# CHANNEL.net
KiCad netlist of a schematic drawn in Altium Designer
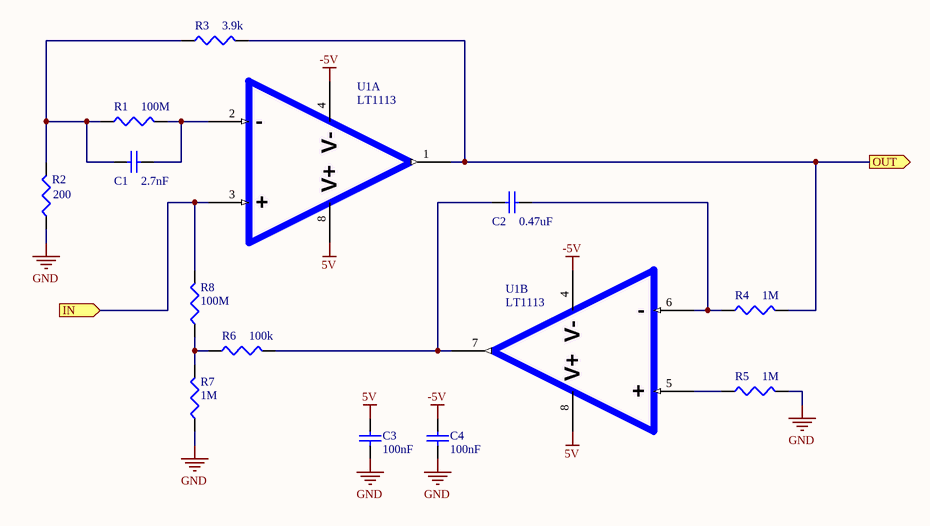
[diagram p0: CHANNEL.SchDoc]

(export (version "E")
  (design (tool "Eeschema 10.0.6"))
  (components
    (comp (ref "C1")
      (value "2.7nF")
      (footprint "1608[0603]")
      (description "Capacitor (Semiconductor SIM Model)")
      (fields (field (name "Comment") "Cap Semi") (field (name "PUBLISHER") "Altium Limited"))
      (libsource (lib "Miscellaneous Devices") (part "Cap Semi"))
    )
    (comp (ref "C2")
      (value "0.47uF")
      (footprint "1608[0603]")
      (description "Capacitor (Semiconductor SIM Model)")
      (fields (field (name "Comment") "Cap Semi") (field (name "PUBLISHER") "Altium Limited"))
      (libsource (lib "Miscellaneous Devices") (part "Cap Semi"))
    )
    (comp (ref "C3")
      (value "100nF")
      (footprint "1608[0603]")
      (description "Capacitor (Semiconductor SIM Model)")
      (fields (field (name "Comment") "Cap Semi") (field (name "PUBLISHER") "Altium Limited"))
      (libsource (lib "Miscellaneous Devices") (part "Cap Semi"))
    )
    (comp (ref "C4")
      (value "100nF")
      (footprint "1608[0603]")
      (description "Capacitor (Semiconductor SIM Model)")
      (fields (field (name "Comment") "Cap Semi") (field (name "PUBLISHER") "Altium Limited"))
      (libsource (lib "Miscellaneous Devices") (part "Cap Semi"))
    )
    (comp (ref "R1")
      (value "100M")
      (footprint "J1-0603")
      (description "Resistor")
      (fields (field (name "Comment") "Res3") (field (name "PUBLISHER") "Altium Limited"))
      (libsource (lib "Miscellaneous Devices") (part "Res3"))
    )
    (comp (ref "R2")
      (value "200")
      (footprint "J1-0603")
      (description "Resistor")
      (fields (field (name "Comment") "Res3") (field (name "PUBLISHER") "Altium Limited"))
      (libsource (lib "Miscellaneous Devices") (part "Res3"))
    )
    (comp (ref "R3")
      (value "3.9k")
      (footprint "J1-0603")
      (description "Resistor")
      (fields (field (name "Comment") "Res3") (field (name "PUBLISHER") "Altium Limited"))
      (libsource (lib "Miscellaneous Devices") (part "Res3"))
    )
    (comp (ref "R4")
      (value "1M")
      (footprint "J1-0603")
      (description "Resistor")
      (fields (field (name "Comment") "Res3") (field (name "PUBLISHER") "Altium Limited"))
      (libsource (lib "Miscellaneous Devices") (part "Res3"))
    )
    (comp (ref "R5")
      (value "1M")
      (footprint "J1-0603")
      (description "Resistor")
      (fields (field (name "Comment") "Res3") (field (name "PUBLISHER") "Altium Limited"))
      (libsource (lib "Miscellaneous Devices") (part "Res3"))
    )
    (comp (ref "R6")
      (value "100k")
      (footprint "J1-0603")
      (description "Resistor")
      (fields (field (name "Comment") "Res3") (field (name "PUBLISHER") "Altium Limited"))
      (libsource (lib "Miscellaneous Devices") (part "Res3"))
    )
    (comp (ref "R7")
      (value "1M")
      (footprint "J1-0603")
      (description "Resistor")
      (fields (field (name "Comment") "Res3") (field (name "PUBLISHER") "Altium Limited"))
      (libsource (lib "Miscellaneous Devices") (part "Res3"))
    )
    (comp (ref "R8")
      (value "100M")
      (footprint "J1-0603")
      (description "Resistor")
      (fields (field (name "Comment") "Res3") (field (name "PUBLISHER") "Altium Limited"))
      (libsource (lib "Miscellaneous Devices") (part "Res3"))
    )
    (comp (ref "U1")
      (value "LT1113")
      (footprint "SO8_L")
      (description "LT1113 Opamp")
      (libsource (lib "Schlib") (part "LT1113"))
    )
  )
  (nets
    (net (code "1") (name "-5V") (class "Default")
      (node (ref "C4") (pin "2") (pinfunction "2_2") (pintype "passive"))
      (node (ref "U1") (pin "4") (pinfunction "V-_4") (pintype "power_in"))
    )
    (net (code "2") (name "/IN") (class "Default")
      (node (ref "R8") (pin "2") (pinfunction "2_2") (pintype "passive"))
      (node (ref "U1") (pin "3") (pinfunction "+_3") (pintype "input"))
    )
    (net (code "3") (name "/OUT") (class "Default")
      (node (ref "R3") (pin "2") (pinfunction "2_2") (pintype "passive"))
      (node (ref "R4") (pin "2") (pinfunction "2_2") (pintype "passive"))
      (node (ref "U1") (pin "1") (pinfunction "OUTA_1") (pintype "output"))
    )
    (net (code "4") (name "5V") (class "Default")
      (node (ref "C3") (pin "2") (pinfunction "2_2") (pintype "passive"))
      (node (ref "U1") (pin "8") (pinfunction "V+_8") (pintype "power_in"))
    )
    (net (code "5") (name "GND") (class "Default")
      (node (ref "C3") (pin "1") (pinfunction "1_1") (pintype "passive"))
      (node (ref "C4") (pin "1") (pinfunction "1_1") (pintype "passive"))
      (node (ref "R2") (pin "1") (pinfunction "1_1") (pintype "passive"))
      (node (ref "R5") (pin "2") (pinfunction "2_2") (pintype "passive"))
      (node (ref "R7") (pin "1") (pinfunction "1_1") (pintype "passive"))
    )
    (net (code "6") (name "Net-(C1-Pad1)") (class "Default")
      (node (ref "C1") (pin "1") (pinfunction "1_1") (pintype "passive"))
      (node (ref "R1") (pin "1") (pinfunction "1_1") (pintype "passive"))
      (node (ref "R2") (pin "2") (pinfunction "2_2") (pintype "passive"))
      (node (ref "R3") (pin "1") (pinfunction "1_1") (pintype "passive"))
    )
    (net (code "7") (name "Net-(R6-Pad1)") (class "Default")
      (node (ref "R6") (pin "1") (pinfunction "1_1") (pintype "passive"))
      (node (ref "R7") (pin "2") (pinfunction "2_2") (pintype "passive"))
      (node (ref "R8") (pin "1") (pinfunction "1_1") (pintype "passive"))
    )
    (net (code "8") (name "Net-(U1A--)") (class "Default")
      (node (ref "C1") (pin "2") (pinfunction "2_2") (pintype "passive"))
      (node (ref "R1") (pin "2") (pinfunction "2_2") (pintype "passive"))
      (node (ref "U1") (pin "2") (pinfunction "-_2") (pintype "input"))
    )
    (net (code "9") (name "Net-(U1B-+)") (class "Default")
      (node (ref "R5") (pin "1") (pinfunction "1_1") (pintype "passive"))
      (node (ref "U1") (pin "5") (pinfunction "+_5") (pintype "input"))
    )
    (net (code "10") (name "Net-(U1B--)") (class "Default")
      (node (ref "C2") (pin "2") (pinfunction "2_2") (pintype "passive"))
      (node (ref "R4") (pin "1") (pinfunction "1_1") (pintype "passive"))
      (node (ref "U1") (pin "6") (pinfunction "-_6") (pintype "input"))
    )
    (net (code "11") (name "Net-(U1B-OUTA)") (class "Default")
      (node (ref "C2") (pin "1") (pinfunction "1_1") (pintype "passive"))
      (node (ref "R6") (pin "2") (pinfunction "2_2") (pintype "passive"))
      (node (ref "U1") (pin "7") (pinfunction "OUTA_7") (pintype "output"))
    )
  )
)
